# TI82_matlab.net
KiCad netlist of a schematic drawn in Altium Designer
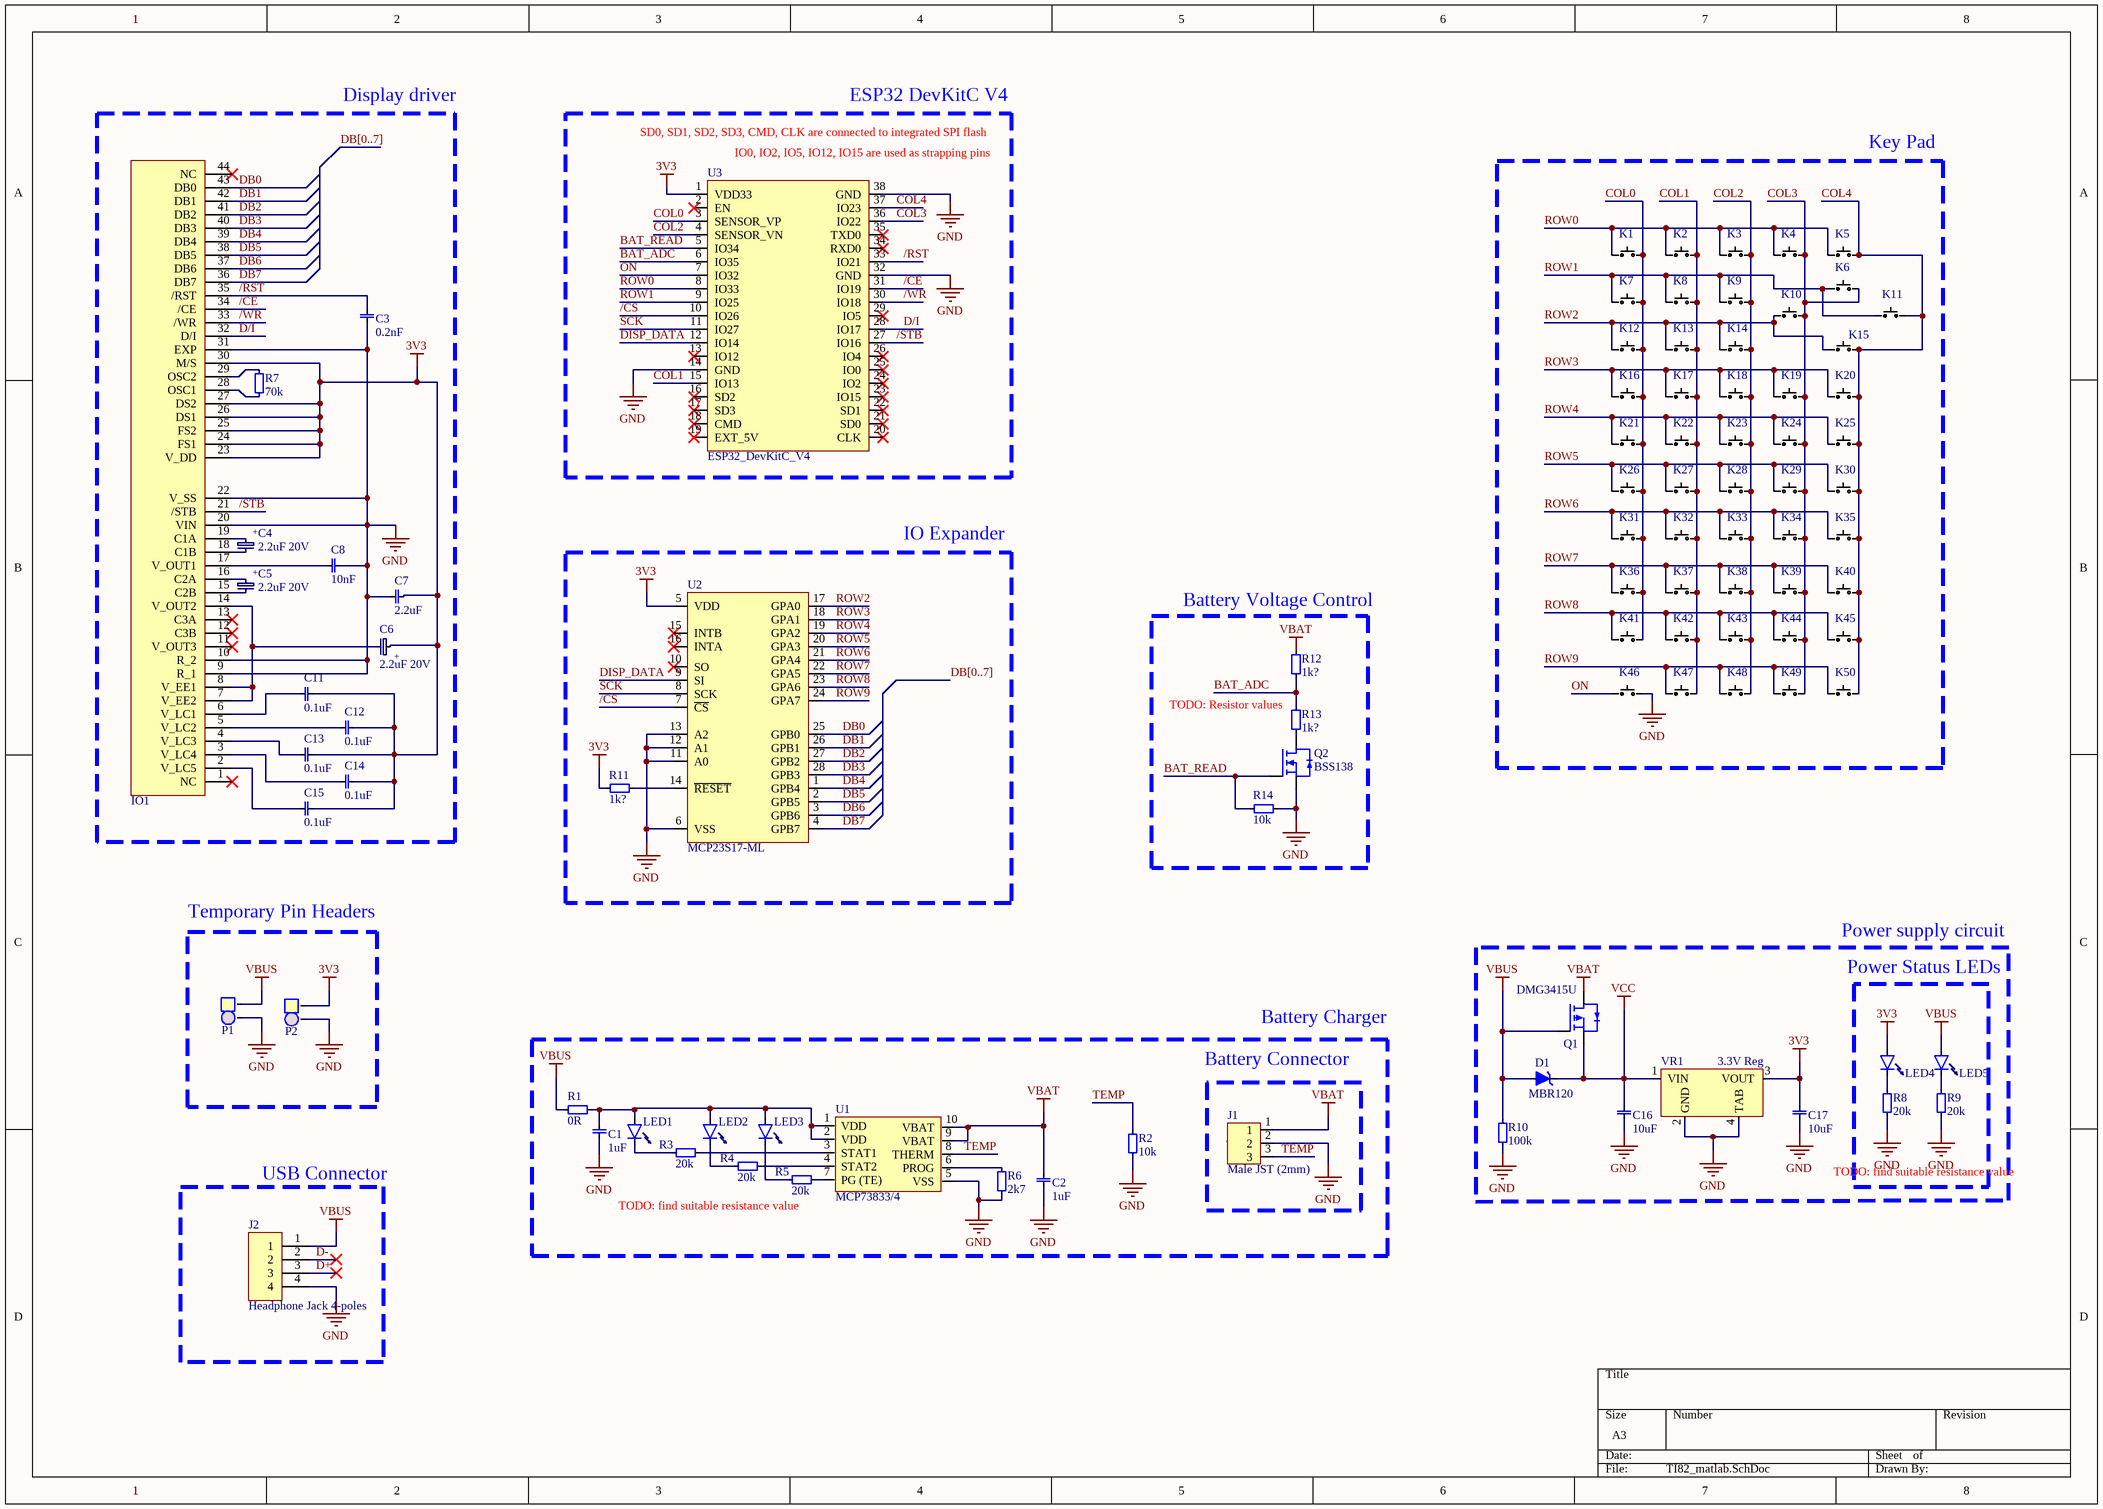
[diagram p0: TI82_matlab.SchDoc]

(export (version "E")
  (design (tool "Eeschema 10.0.6"))
  (components
    (comp (ref "C1")
      (value "1uF")
      (footprint "0603 cap")
      (fields (field (name "Comment") "0603, capacitor"))
      (libsource (lib "jclib") (part "0603, capacitor"))
    )
    (comp (ref "C2")
      (value "1uF")
      (footprint "0603 cap")
      (fields (field (name "Comment") "0603, capacitor"))
      (libsource (lib "jclib") (part "0603, capacitor"))
    )
    (comp (ref "C3")
      (value "0.2nF")
      (footprint "0603 cap")
      (fields (field (name "Comment") "0603, capacitor"))
      (libsource (lib "jclib") (part "0603, capacitor"))
    )
    (comp (ref "C4")
      (value "Cap, bipolar")
      (footprint "CAP 1206 BIPOLAR")
      (fields (field (name "PARAMETER 1") "2.2uF 20V"))
      (libsource (lib "") (part "Cap, bipolar_1"))
    )
    (comp (ref "C5")
      (value "Cap, bipolar")
      (footprint "CAP 1206 BIPOLAR")
      (fields (field (name "PARAMETER 1") "2.2uF 20V"))
      (libsource (lib "") (part "Cap, bipolar_1"))
    )
    (comp (ref "C6")
      (value "Cap, bipolar")
      (footprint "CAP 1206 BIPOLAR")
      (fields (field (name "PARAMETER 1") "2.2uF 20V"))
      (libsource (lib "ti82_lib") (part "Cap, bipolar"))
    )
    (comp (ref "C7")
      (value "2.2uF")
      (footprint "0603 cap")
      (fields (field (name "Comment") "0603, capacitor"))
      (libsource (lib "jclib") (part "0603, capacitor"))
    )
    (comp (ref "C8")
      (value "10nF")
      (footprint "0603 cap")
      (fields (field (name "Comment") "0603, capacitor"))
      (libsource (lib "jclib") (part "0603, capacitor"))
    )
    (comp (ref "C11")
      (value "0.1uF")
      (footprint "0603 cap")
      (fields (field (name "Comment") "0603, capacitor"))
      (libsource (lib "jclib") (part "0603, capacitor"))
    )
    (comp (ref "C12")
      (value "0.1uF")
      (footprint "0603 cap")
      (fields (field (name "Comment") "0603, capacitor"))
      (libsource (lib "jclib") (part "0603, capacitor"))
    )
    (comp (ref "C13")
      (value "0.1uF")
      (footprint "0603 cap")
      (fields (field (name "Comment") "0603, capacitor"))
      (libsource (lib "jclib") (part "0603, capacitor"))
    )
    (comp (ref "C14")
      (value "0.1uF")
      (footprint "0603 cap")
      (fields (field (name "Comment") "0603, capacitor"))
      (libsource (lib "jclib") (part "0603, capacitor"))
    )
    (comp (ref "C15")
      (value "0.1uF")
      (footprint "0603 cap")
      (fields (field (name "Comment") "0603, capacitor"))
      (libsource (lib "jclib") (part "0603, capacitor"))
    )
    (comp (ref "C16")
      (value "10uF")
      (footprint "0603 cap")
      (fields (field (name "Comment") "0603, capacitor"))
      (libsource (lib "jclib") (part "0603, capacitor"))
    )
    (comp (ref "C17")
      (value "10uF")
      (footprint "0603 cap")
      (fields (field (name "Comment") "0603, capacitor"))
      (libsource (lib "jclib") (part "0603, capacitor"))
    )
    (comp (ref "D1")
      (value "MBR120")
      (footprint "SOD-123")
      (description "Schottky Power Rectifier")
      (libsource (lib "proj_lib") (part "MBR120"))
    )
    (comp (ref "IO1")
      (value "Display IO*")
      (footprint "Display IO 44")
      (description "Display Pins for TI-82 STATS")
      (libsource (lib "ti82_lib") (part "Desplay IO 22"))
    )
    (comp (ref "J1")
      (value "Male JST (2mm)")
      (footprint "3P JST Male connector")
      (description "Battery connector")
      (libsource (lib "proj_lib") (part "PCB HEADER 3P"))
    )
    (comp (ref "J2")
      (value "Headphone Jack 4-poles")
      (footprint "Headphone Jack 4-poles")
      (libsource (lib "ti82_lib") (part "Headphone Jack 4-poles"))
    )
    (comp (ref "K1")
      (value "Button Pad")
      (footprint "BUTTON PAD 2")
      (libsource (lib "ti82_lib") (part "Button Pad"))
    )
    (comp (ref "K2")
      (value "Button Pad")
      (footprint "BUTTON PAD 2")
      (libsource (lib "ti82_lib") (part "Button Pad"))
    )
    (comp (ref "K3")
      (value "Button Pad")
      (footprint "BUTTON PAD 2")
      (libsource (lib "ti82_lib") (part "Button Pad"))
    )
    (comp (ref "K4")
      (value "Button Pad")
      (footprint "BUTTON PAD 2")
      (libsource (lib "ti82_lib") (part "Button Pad"))
    )
    (comp (ref "K5")
      (value "Button Pad")
      (footprint "BUTTON PAD 2")
      (libsource (lib "ti82_lib") (part "Button Pad"))
    )
    (comp (ref "K6")
      (value "Button Pad")
      (footprint "BUTTON PAD 2")
      (libsource (lib "ti82_lib") (part "Button Pad"))
    )
    (comp (ref "K7")
      (value "Button Pad")
      (footprint "BUTTON PAD 2")
      (libsource (lib "ti82_lib") (part "Button Pad"))
    )
    (comp (ref "K8")
      (value "Button Pad")
      (footprint "BUTTON PAD 2")
      (libsource (lib "ti82_lib") (part "Button Pad"))
    )
    (comp (ref "K9")
      (value "Button Pad")
      (footprint "BUTTON PAD 2")
      (libsource (lib "ti82_lib") (part "Button Pad"))
    )
    (comp (ref "K10")
      (value "Button Pad")
      (footprint "BUTTON PAD 2")
      (libsource (lib "ti82_lib") (part "Button Pad"))
    )
    (comp (ref "K11")
      (value "Button Pad")
      (footprint "BUTTON PAD 2")
      (libsource (lib "ti82_lib") (part "Button Pad"))
    )
    (comp (ref "K12")
      (value "Button Pad")
      (footprint "BUTTON PAD 2")
      (libsource (lib "ti82_lib") (part "Button Pad"))
    )
    (comp (ref "K13")
      (value "Button Pad")
      (footprint "BUTTON PAD 2")
      (libsource (lib "ti82_lib") (part "Button Pad"))
    )
    (comp (ref "K14")
      (value "Button Pad")
      (footprint "BUTTON PAD 2")
      (libsource (lib "ti82_lib") (part "Button Pad"))
    )
    (comp (ref "K15")
      (value "Button Pad")
      (footprint "BUTTON PAD 2")
      (libsource (lib "ti82_lib") (part "Button Pad"))
    )
    (comp (ref "K16")
      (value "Button Pad")
      (footprint "BUTTON PAD 2")
      (libsource (lib "ti82_lib") (part "Button Pad"))
    )
    (comp (ref "K17")
      (value "Button Pad")
      (footprint "BUTTON PAD 2")
      (libsource (lib "ti82_lib") (part "Button Pad"))
    )
    (comp (ref "K18")
      (value "Button Pad")
      (footprint "BUTTON PAD 2")
      (libsource (lib "ti82_lib") (part "Button Pad"))
    )
    (comp (ref "K19")
      (value "Button Pad")
      (footprint "BUTTON PAD 2")
      (libsource (lib "ti82_lib") (part "Button Pad"))
    )
    (comp (ref "K20")
      (value "Button Pad")
      (footprint "BUTTON PAD 2")
      (libsource (lib "ti82_lib") (part "Button Pad"))
    )
    (comp (ref "K21")
      (value "Button Pad")
      (footprint "BUTTON PAD 2")
      (libsource (lib "ti82_lib") (part "Button Pad"))
    )
    (comp (ref "K22")
      (value "Button Pad")
      (footprint "BUTTON PAD 2")
      (libsource (lib "ti82_lib") (part "Button Pad"))
    )
    (comp (ref "K23")
      (value "Button Pad")
      (footprint "BUTTON PAD 2")
      (libsource (lib "ti82_lib") (part "Button Pad"))
    )
    (comp (ref "K24")
      (value "Button Pad")
      (footprint "BUTTON PAD 2")
      (libsource (lib "ti82_lib") (part "Button Pad"))
    )
    (comp (ref "K25")
      (value "Button Pad")
      (footprint "BUTTON PAD 2")
      (libsource (lib "ti82_lib") (part "Button Pad"))
    )
    (comp (ref "K26")
      (value "Button Pad")
      (footprint "BUTTON PAD 2")
      (libsource (lib "ti82_lib") (part "Button Pad"))
    )
    (comp (ref "K27")
      (value "Button Pad")
      (footprint "BUTTON PAD 2")
      (libsource (lib "ti82_lib") (part "Button Pad"))
    )
    (comp (ref "K28")
      (value "Button Pad")
      (footprint "BUTTON PAD 2")
      (libsource (lib "ti82_lib") (part "Button Pad"))
    )
    (comp (ref "K29")
      (value "Button Pad")
      (footprint "BUTTON PAD 2")
      (libsource (lib "ti82_lib") (part "Button Pad"))
    )
    (comp (ref "K30")
      (value "Button Pad")
      (footprint "BUTTON PAD 2")
      (libsource (lib "ti82_lib") (part "Button Pad"))
    )
    (comp (ref "K31")
      (value "Button Pad")
      (footprint "BUTTON PAD 2")
      (libsource (lib "ti82_lib") (part "Button Pad"))
    )
    (comp (ref "K32")
      (value "Button Pad")
      (footprint "BUTTON PAD 2")
      (libsource (lib "ti82_lib") (part "Button Pad"))
    )
    (comp (ref "K33")
      (value "Button Pad")
      (footprint "BUTTON PAD 2")
      (libsource (lib "ti82_lib") (part "Button Pad"))
    )
    (comp (ref "K34")
      (value "Button Pad")
      (footprint "BUTTON PAD 2")
      (libsource (lib "ti82_lib") (part "Button Pad"))
    )
    (comp (ref "K35")
      (value "Button Pad")
      (footprint "BUTTON PAD 2")
      (libsource (lib "ti82_lib") (part "Button Pad"))
    )
    (comp (ref "K36")
      (value "Button Pad")
      (footprint "BUTTON PAD 2")
      (libsource (lib "ti82_lib") (part "Button Pad"))
    )
    (comp (ref "K37")
      (value "Button Pad")
      (footprint "BUTTON PAD 2")
      (libsource (lib "ti82_lib") (part "Button Pad"))
    )
    (comp (ref "K38")
      (value "Button Pad")
      (footprint "BUTTON PAD 2")
      (libsource (lib "ti82_lib") (part "Button Pad"))
    )
    (comp (ref "K39")
      (value "Button Pad")
      (footprint "BUTTON PAD 2")
      (libsource (lib "ti82_lib") (part "Button Pad"))
    )
    (comp (ref "K40")
      (value "Button Pad")
      (footprint "BUTTON PAD 2")
      (libsource (lib "ti82_lib") (part "Button Pad"))
    )
    (comp (ref "K41")
      (value "Button Pad")
      (footprint "BUTTON PAD 2")
      (libsource (lib "ti82_lib") (part "Button Pad"))
    )
    (comp (ref "K42")
      (value "Button Pad")
      (footprint "BUTTON PAD 2")
      (libsource (lib "ti82_lib") (part "Button Pad"))
    )
    (comp (ref "K43")
      (value "Button Pad")
      (footprint "BUTTON PAD 2")
      (libsource (lib "ti82_lib") (part "Button Pad"))
    )
    (comp (ref "K44")
      (value "Button Pad")
      (footprint "BUTTON PAD 2")
      (libsource (lib "ti82_lib") (part "Button Pad"))
    )
    (comp (ref "K45")
      (value "Button Pad")
      (footprint "BUTTON PAD 2")
      (libsource (lib "ti82_lib") (part "Button Pad"))
    )
    (comp (ref "K46")
      (value "Button Pad")
      (footprint "BUTTON PAD 2")
      (libsource (lib "ti82_lib") (part "Button Pad"))
    )
    (comp (ref "K47")
      (value "Button Pad")
      (footprint "BUTTON PAD 2")
      (libsource (lib "ti82_lib") (part "Button Pad"))
    )
    (comp (ref "K48")
      (value "Button Pad")
      (footprint "BUTTON PAD 2")
      (libsource (lib "ti82_lib") (part "Button Pad"))
    )
    (comp (ref "K49")
      (value "Button Pad")
      (footprint "BUTTON PAD 2")
      (libsource (lib "ti82_lib") (part "Button Pad"))
    )
    (comp (ref "K50")
      (value "Button Pad")
      (footprint "BUTTON PAD 2")
      (libsource (lib "ti82_lib") (part "Button Pad"))
    )
    (comp (ref "LED1")
      (value "0805, LED")
      (footprint "0805_led")
      (libsource (lib "jclib") (part "0805, LED"))
    )
    (comp (ref "LED2")
      (value "0805, LED")
      (footprint "0805_led")
      (libsource (lib "jclib") (part "0805, LED"))
    )
    (comp (ref "LED3")
      (value "0805, LED")
      (footprint "0805_led")
      (libsource (lib "jclib") (part "0805, LED"))
    )
    (comp (ref "LED4")
      (value "0805, LED")
      (footprint "0805_led")
      (libsource (lib "jclib") (part "0805, LED"))
    )
    (comp (ref "LED5")
      (value "0805, LED")
      (footprint "0805_led")
      (libsource (lib "jclib") (part "0805, LED"))
    )
    (comp (ref "P1")
      (value "1x2 Pin Header")
      (footprint "padtwo_L")
      (description "2.54 mm, TH")
      (libsource (lib "jclib") (part "1x2 Pin Header"))
    )
    (comp (ref "P2")
      (value "1x2 Pin Header")
      (footprint "padtwo_L")
      (description "2.54 mm, TH")
      (libsource (lib "jclib") (part "1x2 Pin Header"))
    )
    (comp (ref "Q1")
      (value "DMG3415U")
      (footprint "SOT23")
      (description "P-CHANNEL ENHANCEMENT MODE MOSFET")
      (libsource (lib "proj_lib") (part "DMG3415U"))
    )
    (comp (ref "Q2") (value "BSS138") (footprint "SOT23") (libsource (lib "ti82_lib") (part "BSS138")))
    (comp (ref "R1")
      (value "0R")
      (footprint "0603")
      (fields (field (name "Comment") "0603, resistor"))
      (libsource (lib "jclib") (part "0603, resistor"))
    )
    (comp (ref "R2")
      (value "10k")
      (footprint "0603")
      (fields (field (name "Comment") "0603, resistor"))
      (libsource (lib "jclib") (part "0603, resistor"))
    )
    (comp (ref "R3")
      (value "20k")
      (footprint "0603")
      (fields (field (name "Comment") "0603, resistor"))
      (libsource (lib "jclib") (part "0603, resistor"))
    )
    (comp (ref "R4")
      (value "20k")
      (footprint "0603")
      (fields (field (name "Comment") "0603, resistor"))
      (libsource (lib "jclib") (part "0603, resistor"))
    )
    (comp (ref "R5")
      (value "20k")
      (footprint "0603")
      (fields (field (name "Comment") "0603, resistor"))
      (libsource (lib "jclib") (part "0603, resistor"))
    )
    (comp (ref "R6")
      (value "2k7")
      (footprint "0603")
      (fields (field (name "Comment") "0603, resistor"))
      (libsource (lib "jclib") (part "0603, resistor"))
    )
    (comp (ref "R7")
      (value "70k")
      (footprint "0603")
      (fields (field (name "Comment") "0603, resistor"))
      (libsource (lib "jclib") (part "0603, resistor"))
    )
    (comp (ref "R8")
      (value "20k")
      (footprint "0603")
      (fields (field (name "Comment") "0603, resistor"))
      (libsource (lib "jclib") (part "0603, resistor"))
    )
    (comp (ref "R9")
      (value "20k")
      (footprint "0603")
      (fields (field (name "Comment") "0603, resistor"))
      (libsource (lib "jclib") (part "0603, resistor"))
    )
    (comp (ref "R10")
      (value "100k")
      (footprint "0603")
      (fields (field (name "Comment") "0603, resistor"))
      (libsource (lib "jclib") (part "0603, resistor"))
    )
    (comp (ref "R11")
      (value "1k?")
      (footprint "0603")
      (fields (field (name "Comment") "0603, resistor"))
      (libsource (lib "jclib") (part "0603, resistor"))
    )
    (comp (ref "R12")
      (value "1k?")
      (footprint "0603")
      (fields (field (name "Comment") "0603, resistor"))
      (libsource (lib "jclib") (part "0603, resistor"))
    )
    (comp (ref "R13")
      (value "1k?")
      (footprint "0603")
      (fields (field (name "Comment") "0603, resistor"))
      (libsource (lib "jclib") (part "0603, resistor"))
    )
    (comp (ref "R14")
      (value "10k")
      (footprint "0603")
      (fields (field (name "Comment") "0603, resistor"))
      (libsource (lib "jclib") (part "0603, resistor"))
    )
    (comp (ref "U1")
      (value "MCP73833/4")
      (footprint "MSOP-10")
      (description "Stand-Alone Linear Li-Ion / Li-Polymer Charge\r\nManagement Controller")
      (libsource (lib "proj_lib") (part "MCP73833/4"))
    )
    (comp (ref "U2")
      (value "MCP23S17-ML")
      (footprint "QFN28 0.65 Pitch")
      (libsource (lib "ti82_lib") (part "MCP23S17-ML"))
    )
    (comp (ref "U3")
      (value "ESP32_DevKitC_V4")
      (footprint "ESP32_DevKitC_V4")
      (libsource (lib "ti82_lib") (part "ESP32_DevKitC_V4"))
    )
    (comp (ref "VR1") (value "3.3V Reg") (footprint "SOT223") (libsource (lib "ti82_lib") (part "MCP1826S")))
  )
  (nets
    (net (code "1") (name "/BAT_ADC") (class "Default")
      (node (ref "R12") (pin "1") (pinfunction "1_1") (pintype "passive"))
      (node (ref "R13") (pin "0") (pinfunction "0_0") (pintype "passive"))
      (node (ref "U3") (pin "6") (pinfunction "IO35_6") (pintype "passive"))
    )
    (net (code "2") (name "/BAT_READ") (class "Default")
      (node (ref "Q2") (pin "1") (pinfunction "G_1") (pintype "passive"))
      (node (ref "R14") (pin "0") (pinfunction "0_0") (pintype "passive"))
      (node (ref "U3") (pin "5") (pinfunction "IO34_5") (pintype "passive"))
    )
    (net (code "3") (name "/COL0") (class "Default")
      (node (ref "K1") (pin "1") (pinfunction "1_1") (pintype "passive"))
      (node (ref "K12") (pin "1") (pinfunction "1_1") (pintype "passive"))
      (node (ref "K16") (pin "1") (pinfunction "1_1") (pintype "passive"))
      (node (ref "K21") (pin "1") (pinfunction "1_1") (pintype "passive"))
      (node (ref "K26") (pin "1") (pinfunction "1_1") (pintype "passive"))
      (node (ref "K31") (pin "1") (pinfunction "1_1") (pintype "passive"))
      (node (ref "K36") (pin "1") (pinfunction "1_1") (pintype "passive"))
      (node (ref "K41") (pin "1") (pinfunction "1_1") (pintype "passive"))
      (node (ref "K7") (pin "1") (pinfunction "1_1") (pintype "passive"))
      (node (ref "U3") (pin "3") (pinfunction "SENSOR_VP_3") (pintype "passive"))
    )
    (net (code "4") (name "/COL1") (class "Default")
      (node (ref "K13") (pin "1") (pinfunction "1_1") (pintype "passive"))
      (node (ref "K17") (pin "1") (pinfunction "1_1") (pintype "passive"))
      (node (ref "K2") (pin "1") (pinfunction "1_1") (pintype "passive"))
      (node (ref "K22") (pin "1") (pinfunction "1_1") (pintype "passive"))
      (node (ref "K27") (pin "1") (pinfunction "1_1") (pintype "passive"))
      (node (ref "K32") (pin "1") (pinfunction "1_1") (pintype "passive"))
      (node (ref "K37") (pin "1") (pinfunction "1_1") (pintype "passive"))
      (node (ref "K42") (pin "1") (pinfunction "1_1") (pintype "passive"))
      (node (ref "K47") (pin "1") (pinfunction "1_1") (pintype "passive"))
      (node (ref "K8") (pin "1") (pinfunction "1_1") (pintype "passive"))
      (node (ref "U3") (pin "15") (pinfunction "IO13_15") (pintype "passive"))
    )
    (net (code "5") (name "/COL2") (class "Default")
      (node (ref "K14") (pin "1") (pinfunction "1_1") (pintype "passive"))
      (node (ref "K18") (pin "1") (pinfunction "1_1") (pintype "passive"))
      (node (ref "K23") (pin "1") (pinfunction "1_1") (pintype "passive"))
      (node (ref "K28") (pin "1") (pinfunction "1_1") (pintype "passive"))
      (node (ref "K3") (pin "1") (pinfunction "1_1") (pintype "passive"))
      (node (ref "K33") (pin "1") (pinfunction "1_1") (pintype "passive"))
      (node (ref "K38") (pin "1") (pinfunction "1_1") (pintype "passive"))
      (node (ref "K43") (pin "1") (pinfunction "1_1") (pintype "passive"))
      (node (ref "K48") (pin "1") (pinfunction "1_1") (pintype "passive"))
      (node (ref "K9") (pin "1") (pinfunction "1_1") (pintype "passive"))
      (node (ref "U3") (pin "4") (pinfunction "SENSOR_VN_4") (pintype "passive"))
    )
    (net (code "6") (name "/COL3") (class "Default")
      (node (ref "K10") (pin "1") (pinfunction "1_1") (pintype "passive"))
      (node (ref "K19") (pin "1") (pinfunction "1_1") (pintype "passive"))
      (node (ref "K24") (pin "1") (pinfunction "1_1") (pintype "passive"))
      (node (ref "K29") (pin "1") (pinfunction "1_1") (pintype "passive"))
      (node (ref "K34") (pin "1") (pinfunction "1_1") (pintype "passive"))
      (node (ref "K39") (pin "1") (pinfunction "1_1") (pintype "passive"))
      (node (ref "K4") (pin "1") (pinfunction "1_1") (pintype "passive"))
      (node (ref "K44") (pin "1") (pinfunction "1_1") (pintype "passive"))
      (node (ref "K49") (pin "1") (pinfunction "1_1") (pintype "passive"))
      (node (ref "K6") (pin "1") (pinfunction "1_1") (pintype "passive"))
      (node (ref "U3") (pin "36") (pinfunction "IO22_36") (pintype "passive"))
    )
    (net (code "7") (name "/COL4") (class "Default")
      (node (ref "K11") (pin "1") (pinfunction "1_1") (pintype "passive"))
      (node (ref "K15") (pin "1") (pinfunction "1_1") (pintype "passive"))
      (node (ref "K20") (pin "1") (pinfunction "1_1") (pintype "passive"))
      (node (ref "K25") (pin "1") (pinfunction "1_1") (pintype "passive"))
      (node (ref "K30") (pin "1") (pinfunction "1_1") (pintype "passive"))
      (node (ref "K35") (pin "1") (pinfunction "1_1") (pintype "passive"))
      (node (ref "K40") (pin "1") (pinfunction "1_1") (pintype "passive"))
      (node (ref "K45") (pin "1") (pinfunction "1_1") (pintype "passive"))
      (node (ref "K5") (pin "1") (pinfunction "1_1") (pintype "passive"))
      (node (ref "K50") (pin "1") (pinfunction "1_1") (pintype "passive"))
      (node (ref "U3") (pin "37") (pinfunction "IO23_37") (pintype "passive"))
    )
    (net (code "8") (name "/D+") (class "Default")
      (node (ref "J2") (pin "3") (pinfunction "3_3") (pintype "passive+no_connect"))
    )
    (net (code "9") (name "/D-") (class "Default")
      (node (ref "J2") (pin "2") (pinfunction "2_2") (pintype "passive+no_connect"))
    )
    (net (code "10") (name "/DB0") (class "Default")
      (node (ref "IO1") (pin "43") (pinfunction "DB0_43") (pintype "passive"))
      (node (ref "U2") (pin "25") (pinfunction "GPB0_25") (pintype "passive"))
    )
    (net (code "11") (name "/DB1") (class "Default")
      (node (ref "IO1") (pin "42") (pinfunction "DB1_42") (pintype "passive"))
      (node (ref "U2") (pin "26") (pinfunction "GPB1_26") (pintype "passive"))
    )
    (net (code "12") (name "/DB2") (class "Default")
      (node (ref "IO1") (pin "41") (pinfunction "DB2_41") (pintype "passive"))
      (node (ref "U2") (pin "27") (pinfunction "GPB2_27") (pintype "passive"))
    )
    (net (code "13") (name "/DB3") (class "Default")
      (node (ref "IO1") (pin "40") (pinfunction "DB3_40") (pintype "passive"))
      (node (ref "U2") (pin "28") (pinfunction "GPB3_28") (pintype "passive"))
    )
    (net (code "14") (name "/DB4") (class "Default")
      (node (ref "IO1") (pin "39") (pinfunction "DB4_39") (pintype "passive"))
      (node (ref "U2") (pin "1") (pinfunction "GPB4_1") (pintype "passive"))
    )
    (net (code "15") (name "/DB5") (class "Default")
      (node (ref "IO1") (pin "38") (pinfunction "DB5_38") (pintype "passive"))
      (node (ref "U2") (pin "2") (pinfunction "GPB5_2") (pintype "passive"))
    )
    (net (code "16") (name "/DB6") (class "Default")
      (node (ref "IO1") (pin "37") (pinfunction "DB6_37") (pintype "passive"))
      (node (ref "U2") (pin "3") (pinfunction "GPB6_3") (pintype "passive"))
    )
    (net (code "17") (name "/DB7") (class "Default")
      (node (ref "IO1") (pin "36") (pinfunction "DB7_36") (pintype "passive"))
      (node (ref "U2") (pin "4") (pinfunction "GPB7_4") (pintype "passive"))
    )
    (net (code "19") (name "/DISP_DATA") (class "Default")
      (node (ref "U2") (pin "9") (pinfunction "SI_9") (pintype "passive"))
      (node (ref "U3") (pin "12") (pinfunction "IO14_12") (pintype "passive"))
    )
    (net (code "20") (name "/D{slash}I") (class "Default")
      (node (ref "IO1") (pin "32") (pinfunction "D/I_32") (pintype "passive"))
      (node (ref "U3") (pin "28") (pinfunction "IO17_28") (pintype "passive"))
    )
    (net (code "21") (name "/ON") (class "Default")
      (node (ref "K46") (pin "2") (pinfunction "2_2") (pintype "passive"))
      (node (ref "U3") (pin "7") (pinfunction "IO32_7") (pintype "passive"))
    )
    (net (code "22") (name "/ROW0") (class "Default")
      (node (ref "K1") (pin "2") (pinfunction "2_2") (pintype "passive"))
      (node (ref "K2") (pin "2") (pinfunction "2_2") (pintype "passive"))
      (node (ref "K3") (pin "2") (pinfunction "2_2") (pintype "passive"))
      (node (ref "K4") (pin "2") (pinfunction "2_2") (pintype "passive"))
      (node (ref "K5") (pin "2") (pinfunction "2_2") (pintype "passive"))
      (node (ref "U3") (pin "8") (pinfunction "IO33_8") (pintype "passive"))
    )
    (net (code "23") (name "/ROW1") (class "Default")
      (node (ref "K11") (pin "2") (pinfunction "2_2") (pintype "passive"))
      (node (ref "K6") (pin "2") (pinfunction "2_2") (pintype "passive"))
      (node (ref "K7") (pin "2") (pinfunction "2_2") (pintype "passive"))
      (node (ref "K8") (pin "2") (pinfunction "2_2") (pintype "passive"))
      (node (ref "K9") (pin "2") (pinfunction "2_2") (pintype "passive"))
      (node (ref "U3") (pin "9") (pinfunction "IO25_9") (pintype "passive"))
    )
    (net (code "24") (name "/ROW2") (class "Default")
      (node (ref "K10") (pin "2") (pinfunction "2_2") (pintype "passive"))
      (node (ref "K12") (pin "2") (pinfunction "2_2") (pintype "passive"))
      (node (ref "K13") (pin "2") (pinfunction "2_2") (pintype "passive"))
      (node (ref "K14") (pin "2") (pinfunction "2_2") (pintype "passive"))
      (node (ref "K15") (pin "2") (pinfunction "2_2") (pintype "passive"))
      (node (ref "U2") (pin "17") (pinfunction "GPA0_17") (pintype "passive"))
    )
    (net (code "25") (name "/ROW3") (class "Default")
      (node (ref "K16") (pin "2") (pinfunction "2_2") (pintype "passive"))
      (node (ref "K17") (pin "2") (pinfunction "2_2") (pintype "passive"))
      (node (ref "K18") (pin "2") (pinfunction "2_2") (pintype "passive"))
      (node (ref "K19") (pin "2") (pinfunction "2_2") (pintype "passive"))
      (node (ref "K20") (pin "2") (pinfunction "2_2") (pintype "passive"))
      (node (ref "U2") (pin "18") (pinfunction "GPA1_18") (pintype "passive"))
    )
    (net (code "26") (name "/ROW4") (class "Default")
      (node (ref "K21") (pin "2") (pinfunction "2_2") (pintype "passive"))
      (node (ref "K22") (pin "2") (pinfunction "2_2") (pintype "passive"))
      (node (ref "K23") (pin "2") (pinfunction "2_2") (pintype "passive"))
      (node (ref "K24") (pin "2") (pinfunction "2_2") (pintype "passive"))
      (node (ref "K25") (pin "2") (pinfunction "2_2") (pintype "passive"))
      (node (ref "U2") (pin "19") (pinfunction "GPA2_19") (pintype "passive"))
    )
    (net (code "27") (name "/ROW5") (class "Default")
      (node (ref "K26") (pin "2") (pinfunction "2_2") (pintype "passive"))
      (node (ref "K27") (pin "2") (pinfunction "2_2") (pintype "passive"))
      (node (ref "K28") (pin "2") (pinfunction "2_2") (pintype "passive"))
      (node (ref "K29") (pin "2") (pinfunction "2_2") (pintype "passive"))
      (node (ref "K30") (pin "2") (pinfunction "2_2") (pintype "passive"))
      (node (ref "U2") (pin "20") (pinfunction "GPA3_20") (pintype "passive"))
    )
    (net (code "28") (name "/ROW6") (class "Default")
      (node (ref "K31") (pin "2") (pinfunction "2_2") (pintype "passive"))
      (node (ref "K32") (pin "2") (pinfunction "2_2") (pintype "passive"))
      (node (ref "K33") (pin "2") (pinfunction "2_2") (pintype "passive"))
      (node (ref "K34") (pin "2") (pinfunction "2_2") (pintype "passive"))
      (node (ref "K35") (pin "2") (pinfunction "2_2") (pintype "passive"))
      (node (ref "U2") (pin "21") (pinfunction "GPA4_21") (pintype "passive"))
    )
    (net (code "29") (name "/ROW7") (class "Default")
      (node (ref "K36") (pin "2") (pinfunction "2_2") (pintype "passive"))
      (node (ref "K37") (pin "2") (pinfunction "2_2") (pintype "passive"))
      (node (ref "K38") (pin "2") (pinfunction "2_2") (pintype "passive"))
      (node (ref "K39") (pin "2") (pinfunction "2_2") (pintype "passive"))
      (node (ref "K40") (pin "2") (pinfunction "2_2") (pintype "passive"))
      (node (ref "U2") (pin "22") (pinfunction "GPA5_22") (pintype "passive"))
    )
    (net (code "30") (name "/ROW8") (class "Default")
      (node (ref "K41") (pin "2") (pinfunction "2_2") (pintype "passive"))
      (node (ref "K42") (pin "2") (pinfunction "2_2") (pintype "passive"))
      (node (ref "K43") (pin "2") (pinfunction "2_2") (pintype "passive"))
      (node (ref "K44") (pin "2") (pinfunction "2_2") (pintype "passive"))
      (node (ref "K45") (pin "2") (pinfunction "2_2") (pintype "passive"))
      (node (ref "U2") (pin "23") (pinfunction "GPA6_23") (pintype "passive"))
    )
    (net (code "31") (name "/ROW9") (class "Default")
      (node (ref "K47") (pin "2") (pinfunction "2_2") (pintype "passive"))
      (node (ref "K48") (pin "2") (pinfunction "2_2") (pintype "passive"))
      (node (ref "K49") (pin "2") (pinfunction "2_2") (pintype "passive"))
      (node (ref "K50") (pin "2") (pinfunction "2_2") (pintype "passive"))
      (node (ref "U2") (pin "24") (pinfunction "GPA7_24") (pintype "passive"))
    )
    (net (code "32") (name "/SCK") (class "Default")
      (node (ref "U2") (pin "8") (pinfunction "SCK_8") (pintype "passive"))
      (node (ref "U3") (pin "11") (pinfunction "IO27_11") (pintype "passive"))
    )
    (net (code "33") (name "/TEMP") (class "Default")
      (node (ref "J1") (pin "3") (pinfunction "3_3") (pintype "passive"))
      (node (ref "R2") (pin "0") (pinfunction "0_0") (pintype "passive"))
      (node (ref "U1") (pin "8") (pinfunction "THERM_8") (pintype "passive"))
    )
    (net (code "34") (name "/{slash}CE") (class "Default")
      (node (ref "IO1") (pin "34") (pinfunction "/CE_34") (pintype "passive"))
      (node (ref "U3") (pin "31") (pinfunction "IO19_31") (pintype "passive"))
    )
    (net (code "35") (name "/{slash}CS") (class "Default")
      (node (ref "U2") (pin "7") (pinfunction "~{CS}_7") (pintype "passive"))
      (node (ref "U3") (pin "10") (pinfunction "IO26_10") (pintype "passive"))
    )
    (net (code "36") (name "/{slash}RST") (class "Default")
      (node (ref "C3") (pin "1") (pinfunction "1_1") (pintype "passive"))
      (node (ref "IO1") (pin "35") (pinfunction "/RST_35") (pintype "passive"))
      (node (ref "U3") (pin "33") (pinfunction "IO21_33") (pintype "passive"))
    )
    (net (code "37") (name "/{slash}STB") (class "Default")
      (node (ref "IO1") (pin "21") (pinfunction "/STB_21") (pintype "passive"))
      (node (ref "U3") (pin "27") (pinfunction "IO16_27") (pintype "passive"))
    )
    (net (code "38") (name "/{slash}WR") (class "Default")
      (node (ref "IO1") (pin "33") (pinfunction "/WR_33") (pintype "passive"))
      (node (ref "U3") (pin "30") (pinfunction "IO18_30") (pintype "passive"))
    )
    (net (code "39") (name "3V3") (class "Default")
      (node (ref "C11") (pin "0") (pinfunction "0_0") (pintype "passive"))
      (node (ref "C12") (pin "0") (pinfunction "0_0") (pintype "passive"))
      (node (ref "C13") (pin "0") (pinfunction "0_0") (pintype "passive"))
      (node (ref "C14") (pin "0") (pinfunction "0_0") (pintype "passive"))
      (node (ref "C15") (pin "0") (pinfunction "0_0") (pintype "passive"))
      (node (ref "C17") (pin "1") (pinfunction "1_1") (pintype "passive"))
      (node (ref "C6") (pin "1") (pinfunction "1_1") (pintype "passive"))
      (node (ref "C7") (pin "0") (pinfunction "0_0") (pintype "passive"))
      (node (ref "IO1") (pin "23") (pinfunction "V_DD_23") (pintype "passive"))
      (node (ref "IO1") (pin "24") (pinfunction "FS1_24") (pintype "passive"))
      (node (ref "IO1") (pin "25") (pinfunction "FS2_25") (pintype "passive"))
      (node (ref "IO1") (pin "26") (pinfunction "DS1_26") (pintype "passive"))
      (node (ref "IO1") (pin "27") (pinfunction "DS2_27") (pintype "passive"))
      (node (ref "IO1") (pin "30") (pinfunction "M/S_30") (pintype "passive"))
      (node (ref "LED4") (pin "1") (pinfunction "1_1") (pintype "passive"))
      (node (ref "P2") (pin "1") (pinfunction "1_1") (pintype "passive"))
      (node (ref "R11") (pin "1") (pinfunction "1_1") (pintype "passive"))
      (node (ref "U2") (pin "5") (pinfunction "VDD_5") (pintype "passive"))
      (node (ref "U3") (pin "1") (pinfunction "VDD33_1") (pintype "passive"))
      (node (ref "VR1") (pin "3") (pinfunction "VOUT_3") (pintype "passive"))
    )
    (net (code "40") (name "GND") (class "Default")
      (node (ref "C1") (pin "0") (pinfunction "0_0") (pintype "passive"))
      (node (ref "C16") (pin "0") (pinfunction "0_0") (pintype "passive"))
      (node (ref "C17") (pin "0") (pinfunction "0_0") (pintype "passive"))
      (node (ref "C2") (pin "0") (pinfunction "0_0") (pintype "passive"))
      (node (ref "C3") (pin "0") (pinfunction "0_0") (pintype "passive"))
      (node (ref "C7") (pin "1") (pinfunction "1_1") (pintype "passive"))
      (node (ref "C8") (pin "0") (pinfunction "0_0") (pintype "passive"))
      (node (ref "IO1") (pin "10") (pinfunction "R_2_10") (pintype "passive"))
      (node (ref "IO1") (pin "20") (pinfunction "VIN_20") (pintype "passive"))
      (node (ref "IO1") (pin "22") (pinfunction "V_SS_22") (pintype "passive"))
      (node (ref "IO1") (pin "31") (pinfunction "EXP_31") (pintype "passive"))
      (node (ref "IO1") (pin "9") (pinfunction "R_1_9") (pintype "passive"))
      (node (ref "J1") (pin "2") (pinfunction "2_2") (pintype "passive"))
      (node (ref "J2") (pin "4") (pinfunction "4_4") (pintype "passive"))
      (node (ref "K46") (pin "1") (pinfunction "1_1") (pintype "passive"))
      (node (ref "P1") (pin "2") (pinfunction "2_2") (pintype "passive"))
      (node (ref "P2") (pin "2") (pinfunction "2_2") (pintype "passive"))
      (node (ref "Q2") (pin "2") (pinfunction "S_2") (pintype "passive"))
      (node (ref "R10") (pin "1") (pinfunction "1_1") (pintype "passive"))
      (node (ref "R14") (pin "1") (pinfunction "1_1") (pintype "passive"))
      (node (ref "R2") (pin "1") (pinfunction "1_1") (pintype "passive"))
      (node (ref "R6") (pin "1") (pinfunction "1_1") (pintype "passive"))
      (node (ref "R8") (pin "1") (pinfunction "1_1") (pintype "passive"))
      (node (ref "R9") (pin "1") (pinfunction "1_1") (pintype "passive"))
      (node (ref "U1") (pin "5") (pinfunction "VSS_5") (pintype "passive"))
      (node (ref "U2") (pin "11") (pinfunction "A0_11") (pintype "passive"))
      (node (ref "U2") (pin "12") (pinfunction "A1_12") (pintype "passive"))
      (node (ref "U2") (pin "13") (pinfunction "A2_13") (pintype "passive"))
      (node (ref "U2") (pin "6") (pinfunction "VSS_6") (pintype "passive"))
      (node (ref "U3") (pin "14") (pinfunction "GND_14") (pintype "passive"))
      (node (ref "U3") (pin "32") (pinfunction "GND_32") (pintype "passive"))
      (node (ref "U3") (pin "38") (pinfunction "GND_38") (pintype "passive"))
      (node (ref "VR1") (pin "2") (pinfunction "GND_2") (pintype "passive"))
      (node (ref "VR1") (pin "4") (pinfunction "TAB_4") (pintype "passive"))
    )
    (net (code "41") (name "Net-(C1-Pad1)") (class "Default")
      (node (ref "C1") (pin "1") (pinfunction "1_1") (pintype "passive"))
      (node (ref "LED1") (pin "1") (pinfunction "1_1") (pintype "passive"))
      (node (ref "LED2") (pin "1") (pinfunction "1_1") (pintype "passive"))
      (node (ref "LED3") (pin "1") (pinfunction "1_1") (pintype "passive"))
      (node (ref "R1") (pin "1") (pinfunction "1_1") (pintype "passive"))
      (node (ref "U1") (pin "1") (pinfunction "VDD_1") (pintype "passive"))
      (node (ref "U1") (pin "2") (pinfunction "VDD_2") (pintype "passive"))
    )
    (net (code "42") (name "Net-(IO1-C1A)") (class "Default")
      (node (ref "C4") (pin "1") (pinfunction "1_1") (pintype "passive"))
      (node (ref "IO1") (pin "19") (pinfunction "C1A_19") (pintype "passive"))
    )
    (net (code "43") (name "Net-(IO1-C1B)") (class "Default")
      (node (ref "C4") (pin "0") (pinfunction "0_0") (pintype "passive"))
      (node (ref "IO1") (pin "18") (pinfunction "C1B_18") (pintype "passive"))
    )
    (net (code "44") (name "Net-(IO1-C2A)") (class "Default")
      (node (ref "C5") (pin "1") (pinfunction "1_1") (pintype "passive"))
      (node (ref "IO1") (pin "16") (pinfunction "C2A_16") (pintype "passive"))
    )
    (net (code "45") (name "Net-(IO1-C2B)") (class "Default")
      (node (ref "C5") (pin "0") (pinfunction "0_0") (pintype "passive"))
      (node (ref "IO1") (pin "15") (pinfunction "C2B_15") (pintype "passive"))
    )
    (net (code "46") (name "Net-(IO1-OSC1)") (class "Default")
      (node (ref "IO1") (pin "28") (pinfunction "OSC1_28") (pintype "passive"))
      (node (ref "R7") (pin "1") (pinfunction "1_1") (pintype "passive"))
    )
    (net (code "47") (name "Net-(IO1-OSC2)") (class "Default")
      (node (ref "IO1") (pin "29") (pinfunction "OSC2_29") (pintype "passive"))
      (node (ref "R7") (pin "0") (pinfunction "0_0") (pintype "passive"))
    )
    (net (code "48") (name "Net-(IO1-V_EE1)") (class "Default")
      (node (ref "C6") (pin "0") (pinfunction "0_0") (pintype "passive"))
      (node (ref "IO1") (pin "14") (pinfunction "V_OUT2_14") (pintype "passive"))
      (node (ref "IO1") (pin "7") (pinfunction "V_EE2_7") (pintype "passive"))
      (node (ref "IO1") (pin "8") (pinfunction "V_EE1_8") (pintype "passive"))
    )
    (net (code "49") (name "Net-(IO1-V_LC1)") (class "Default")
      (node (ref "C11") (pin "1") (pinfunction "1_1") (pintype "passive"))
      (node (ref "IO1") (pin "6") (pinfunction "V_LC1_6") (pintype "passive"))
    )
    (net (code "50") (name "Net-(IO1-V_LC2)") (class "Default")
      (node (ref "C12") (pin "1") (pinfunction "1_1") (pintype "passive"))
      (node (ref "IO1") (pin "5") (pinfunction "V_LC2_5") (pintype "passive"))
    )
    (net (code "51") (name "Net-(IO1-V_LC3)") (class "Default")
      (node (ref "C13") (pin "1") (pinfunction "1_1") (pintype "passive"))
      (node (ref "IO1") (pin "4") (pinfunction "V_LC3_4") (pintype "passive"))
    )
    (net (code "52") (name "Net-(IO1-V_LC4)") (class "Default")
      (node (ref "C14") (pin "1") (pinfunction "1_1") (pintype "passive"))
      (node (ref "IO1") (pin "3") (pinfunction "V_LC4_3") (pintype "passive"))
    )
    (net (code "53") (name "Net-(IO1-V_LC5)") (class "Default")
      (node (ref "C15") (pin "1") (pinfunction "1_1") (pintype "passive"))
      (node (ref "IO1") (pin "2") (pinfunction "V_LC5_2") (pintype "passive"))
    )
    (net (code "54") (name "Net-(IO1-V_OUT1)") (class "Default")
      (node (ref "C8") (pin "1") (pinfunction "1_1") (pintype "passive"))
      (node (ref "IO1") (pin "17") (pinfunction "V_OUT1_17") (pintype "passive"))
    )
    (net (code "55") (name "Net-(LED1-Cathode)") (class "Default")
      (node (ref "LED1") (pin "0") (pinfunction "Cathode_0") (pintype "passive"))
      (node (ref "R3") (pin "0") (pinfunction "0_0") (pintype "passive"))
    )
    (net (code "56") (name "Net-(LED2-Cathode)") (class "Default")
      (node (ref "LED2") (pin "0") (pinfunction "Cathode_0") (pintype "passive"))
      (node (ref "R4") (pin "0") (pinfunction "0_0") (pintype "passive"))
    )
    (net (code "57") (name "Net-(LED3-Cathode)") (class "Default")
      (node (ref "LED3") (pin "0") (pinfunction "Cathode_0") (pintype "passive"))
      (node (ref "R5") (pin "0") (pinfunction "0_0") (pintype "passive"))
    )
    (net (code "58") (name "Net-(LED4-Cathode)") (class "Default")
      (node (ref "LED4") (pin "0") (pinfunction "Cathode_0") (pintype "passive"))
      (node (ref "R8") (pin "0") (pinfunction "0_0") (pintype "passive"))
    )
    (net (code "59") (name "Net-(LED5-Cathode)") (class "Default")
      (node (ref "LED5") (pin "0") (pinfunction "Cathode_0") (pintype "passive"))
      (node (ref "R9") (pin "0") (pinfunction "0_0") (pintype "passive"))
    )
    (net (code "60") (name "Net-(Q2-D)") (class "Default")
      (node (ref "Q2") (pin "3") (pinfunction "D_3") (pintype "passive"))
      (node (ref "R13") (pin "1") (pinfunction "1_1") (pintype "passive"))
    )
    (net (code "61") (name "Net-(U1-PG_(TE))") (class "Default")
      (node (ref "R5") (pin "1") (pinfunction "1_1") (pintype "passive"))
      (node (ref "U1") (pin "7") (pinfunction "PG_(TE)_7") (pintype "passive"))
    )
    (net (code "62") (name "Net-(U1-PROG)") (class "Default")
      (node (ref "R6") (pin "0") (pinfunction "0_0") (pintype "passive"))
      (node (ref "U1") (pin "6") (pinfunction "PROG_6") (pintype "passive"))
    )
    (net (code "63") (name "Net-(U1-STAT1)") (class "Default")
      (node (ref "R3") (pin "1") (pinfunction "1_1") (pintype "passive"))
      (node (ref "U1") (pin "3") (pinfunction "STAT1_3") (pintype "passive"))
    )
    (net (code "64") (name "Net-(U1-STAT2)") (class "Default")
      (node (ref "R4") (pin "1") (pinfunction "1_1") (pintype "passive"))
      (node (ref "U1") (pin "4") (pinfunction "STAT2_4") (pintype "passive"))
    )
    (net (code "65") (name "Net-(U2-~{RESET})") (class "Default")
      (node (ref "R11") (pin "0") (pinfunction "0_0") (pintype "passive"))
      (node (ref "U2") (pin "14") (pinfunction "~{RESET}_14") (pintype "passive"))
    )
    (net (code "66") (name "VBAT") (class "Default")
      (node (ref "C2") (pin "1") (pinfunction "1_1") (pintype "passive"))
      (node (ref "J1") (pin "1") (pinfunction "1_1") (pintype "passive"))
      (node (ref "Q1") (pin "3") (pinfunction "D_3") (pintype "passive"))
      (node (ref "R12") (pin "0") (pinfunction "0_0") (pintype "passive"))
      (node (ref "U1") (pin "10") (pinfunction "VBAT_10") (pintype "passive"))
      (node (ref "U1") (pin "9") (pinfunction "VBAT_9") (pintype "passive"))
    )
    (net (code "67") (name "VBUS") (class "Default")
      (node (ref "D1") (pin "2") (pinfunction "2_2") (pintype "passive"))
      (node (ref "J2") (pin "1") (pinfunction "1_1") (pintype "passive"))
      (node (ref "LED5") (pin "1") (pinfunction "1_1") (pintype "passive"))
      (node (ref "P1") (pin "1") (pinfunction "1_1") (pintype "passive"))
      (node (ref "Q1") (pin "1") (pinfunction "G_1") (pintype "passive"))
      (node (ref "R1") (pin "0") (pinfunction "0_0") (pintype "passive"))
      (node (ref "R10") (pin "0") (pinfunction "0_0") (pintype "passive"))
    )
    (net (code "68") (name "VCC") (class "Default")
      (node (ref "C16") (pin "1") (pinfunction "1_1") (pintype "passive"))
      (node (ref "D1") (pin "1") (pinfunction "1_1") (pintype "passive"))
      (node (ref "Q1") (pin "2") (pinfunction "S_2") (pintype "passive"))
      (node (ref "VR1") (pin "1") (pinfunction "VIN_1") (pintype "passive"))
    )
    (net (code "69") (name "unconnected-(IO1-C3A-Pad13)") (class "Default")
      (node (ref "IO1") (pin "13") (pinfunction "C3A_13") (pintype "passive+no_connect"))
    )
    (net (code "70") (name "unconnected-(IO1-C3B-Pad12)") (class "Default")
      (node (ref "IO1") (pin "12") (pinfunction "C3B_12") (pintype "passive+no_connect"))
    )
    (net (code "71") (name "unconnected-(IO1-NC-Pad1)") (class "Default")
      (node (ref "IO1") (pin "1") (pinfunction "NC_1") (pintype "passive+no_connect"))
    )
    (net (code "72") (name "unconnected-(IO1-NC-Pad44)") (class "Default")
      (node (ref "IO1") (pin "44") (pinfunction "NC_44") (pintype "passive+no_connect"))
    )
    (net (code "73") (name "unconnected-(IO1-V_OUT3-Pad11)") (class "Default")
      (node (ref "IO1") (pin "11") (pinfunction "V_OUT3_11") (pintype "passive+no_connect"))
    )
    (net (code "74") (name "unconnected-(U2-INTA-Pad16)") (class "Default")
      (node (ref "U2") (pin "16") (pinfunction "INTA_16") (pintype "passive+no_connect"))
    )
    (net (code "75") (name "unconnected-(U2-INTB-Pad15)") (class "Default")
      (node (ref "U2") (pin "15") (pinfunction "INTB_15") (pintype "passive+no_connect"))
    )
    (net (code "76") (name "unconnected-(U2-SO-Pad10)") (class "Default")
      (node (ref "U2") (pin "10") (pinfunction "SO_10") (pintype "passive+no_connect"))
    )
    (net (code "77") (name "unconnected-(U3-CLK-Pad20)") (class "Default")
      (node (ref "U3") (pin "20") (pinfunction "CLK_20") (pintype "passive+no_connect"))
    )
    (net (code "78") (name "unconnected-(U3-CMD-Pad18)") (class "Default")
      (node (ref "U3") (pin "18") (pinfunction "CMD_18") (pintype "passive+no_connect"))
    )
    (net (code "79") (name "unconnected-(U3-EN-Pad2)") (class "Default")
      (node (ref "U3") (pin "2") (pinfunction "EN_2") (pintype "passive+no_connect"))
    )
    (net (code "80") (name "unconnected-(U3-EXT_5V-Pad19)") (class "Default")
      (node (ref "U3") (pin "19") (pinfunction "EXT_5V_19") (pintype "passive+no_connect"))
    )
    (net (code "81") (name "unconnected-(U3-IO0-Pad25)") (class "Default")
      (node (ref "U3") (pin "25") (pinfunction "IO0_25") (pintype "passive+no_connect"))
    )
    (net (code "82") (name "unconnected-(U3-IO2-Pad24)") (class "Default")
      (node (ref "U3") (pin "24") (pinfunction "IO2_24") (pintype "passive+no_connect"))
    )
    (net (code "83") (name "unconnected-(U3-IO4-Pad26)") (class "Default")
      (node (ref "U3") (pin "26") (pinfunction "IO4_26") (pintype "passive+no_connect"))
    )
    (net (code "84") (name "unconnected-(U3-IO5-Pad29)") (class "Default")
      (node (ref "U3") (pin "29") (pinfunction "IO5_29") (pintype "passive+no_connect"))
    )
    (net (code "85") (name "unconnected-(U3-IO12-Pad13)") (class "Default")
      (node (ref "U3") (pin "13") (pinfunction "IO12_13") (pintype "passive+no_connect"))
    )
    (net (code "86") (name "unconnected-(U3-IO15-Pad23)") (class "Default")
      (node (ref "U3") (pin "23") (pinfunction "IO15_23") (pintype "passive+no_connect"))
    )
    (net (code "87") (name "unconnected-(U3-RXD0-Pad34)") (class "Default")
      (node (ref "U3") (pin "34") (pinfunction "RXD0_34") (pintype "passive+no_connect"))
    )
    (net (code "88") (name "unconnected-(U3-SD0-Pad21)") (class "Default")
      (node (ref "U3") (pin "21") (pinfunction "SD0_21") (pintype "passive+no_connect"))
    )
    (net (code "89") (name "unconnected-(U3-SD1-Pad22)") (class "Default")
      (node (ref "U3") (pin "22") (pinfunction "SD1_22") (pintype "passive+no_connect"))
    )
    (net (code "90") (name "unconnected-(U3-SD2-Pad16)") (class "Default")
      (node (ref "U3") (pin "16") (pinfunction "SD2_16") (pintype "passive+no_connect"))
    )
    (net (code "91") (name "unconnected-(U3-SD3-Pad17)") (class "Default")
      (node (ref "U3") (pin "17") (pinfunction "SD3_17") (pintype "passive+no_connect"))
    )
    (net (code "92") (name "unconnected-(U3-TXD0-Pad35)") (class "Default")
      (node (ref "U3") (pin "35") (pinfunction "TXD0_35") (pintype "passive+no_connect"))
    )
  )
)
